# TopLevel.net
KiCad netlist of a schematic drawn in Altium Designer
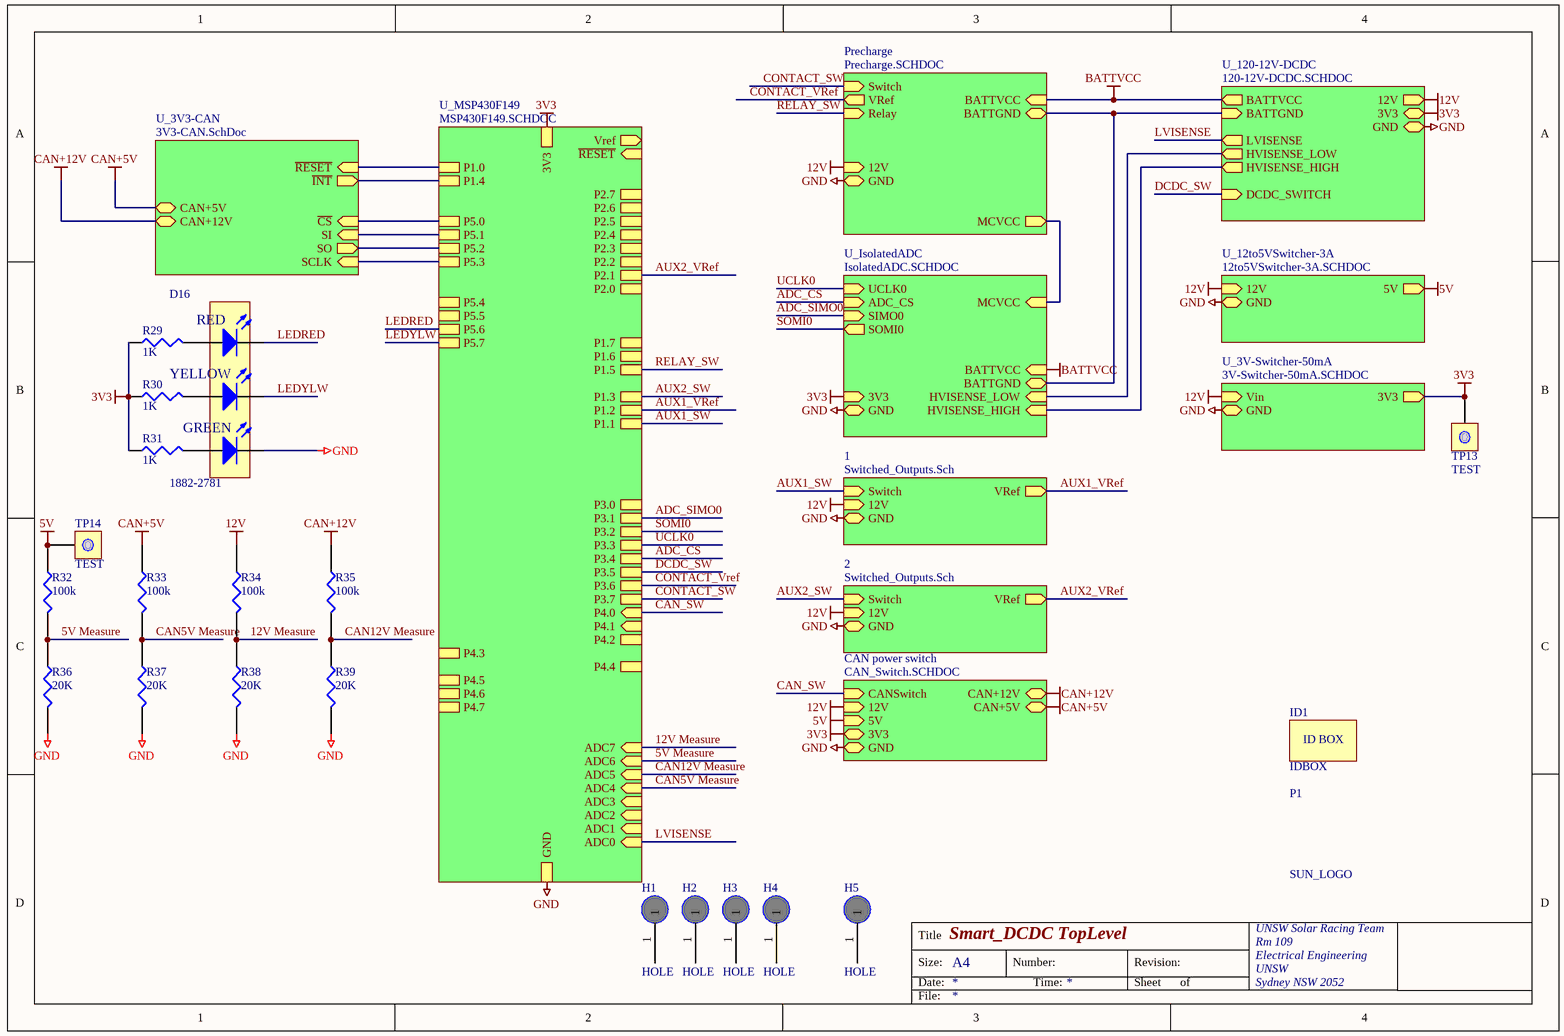
[diagram p0: TopLevel.SCHDOC]

(export (version "E")
  (design (tool "Eeschema 10.0.6"))
  (components
    (comp (ref "D16")
      (value "1882-2781")
      (footprint "LED_TRILEVEL")
      (description "Three level LED")
      (libsource (lib "RCLDQ") (part "LED-TRILEVEL"))
    )
    (comp (ref "H1")
      (value "HOLE")
      (footprint "#6")
      (description "Hole")
      (libsource (lib "Miscellaneous") (part "HOLE"))
    )
    (comp (ref "H2")
      (value "HOLE")
      (footprint "#6")
      (description "Hole")
      (libsource (lib "Miscellaneous") (part "HOLE"))
    )
    (comp (ref "H3")
      (value "HOLE")
      (footprint "#6")
      (description "Hole")
      (libsource (lib "Miscellaneous") (part "HOLE"))
    )
    (comp (ref "H4")
      (value "HOLE")
      (footprint "#6")
      (description "Hole")
      (libsource (lib "Miscellaneous") (part "HOLE"))
    )
    (comp (ref "H5")
      (value "HOLE")
      (footprint "#6")
      (description "Hole")
      (libsource (lib "Miscellaneous") (part "HOLE"))
    )
    (comp (ref "ID1") (value "IDBOX") (footprint "IDBOX") (libsource (lib "Miscellaneous") (part "IDBOX")))
    (comp (ref "P1")
      (value "SUN_LOGO")
      (footprint "SUNSWIFTLOGO")
      (libsource (lib "Miscellaneous") (part "SUN_LOGO"))
    )
    (comp (ref "R29")
      (value "1K")
      (footprint "0603")
      (description "Resistor")
      (libsource (lib "RCLDQ") (part "RES1"))
    )
    (comp (ref "R30")
      (value "1K")
      (footprint "0603")
      (description "Resistor")
      (libsource (lib "RCLDQ") (part "RES1"))
    )
    (comp (ref "R31")
      (value "1K")
      (footprint "0603")
      (description "Resistor")
      (libsource (lib "RCLDQ") (part "RES1"))
    )
    (comp (ref "R32") (value "100k") (footprint "1206") (libsource (lib "*") (part "RES1")))
    (comp (ref "R33") (value "100k") (footprint "1206") (libsource (lib "*") (part "RES1")))
    (comp (ref "R34") (value "100k") (footprint "1206") (libsource (lib "*") (part "RES1")))
    (comp (ref "R35") (value "100k") (footprint "1206") (libsource (lib "*") (part "RES1")))
    (comp (ref "R36") (value "20K") (footprint "1206") (libsource (lib "*") (part "RES1")))
    (comp (ref "R37") (value "20K") (footprint "1206") (libsource (lib "*") (part "RES1")))
    (comp (ref "R38") (value "20K") (footprint "1206") (libsource (lib "*") (part "RES1")))
    (comp (ref "R39") (value "20K") (footprint "1206") (libsource (lib "*") (part "RES1")))
    (comp (ref "TP13")
      (value "TEST")
      (footprint "TESTPOINT")
      (description "TEST POINT")
      (libsource (lib "Miscellaneous") (part "TEST"))
    )
    (comp (ref "TP14")
      (value "TEST")
      (footprint "TESTPOINT")
      (description "TEST POINT")
      (libsource (lib "") (part "TEST_1"))
    )
  )
  (nets
    (net (code "1") (name "/5V Measure") (class "Default")
      (node (ref "R32") (pin "2") (pinfunction "2_2") (pintype "passive"))
      (node (ref "R36") (pin "1") (pinfunction "1_1") (pintype "passive"))
    )
    (net (code "2") (name "/12V Measure") (class "Default")
      (node (ref "R34") (pin "2") (pinfunction "2_2") (pintype "passive"))
      (node (ref "R38") (pin "1") (pinfunction "1_1") (pintype "passive"))
    )
    (net (code "13") (name "/CAN5V Measure") (class "Default")
      (node (ref "R33") (pin "2") (pinfunction "2_2") (pintype "passive"))
      (node (ref "R37") (pin "1") (pinfunction "1_1") (pintype "passive"))
    )
    (net (code "14") (name "/CAN12V Measure") (class "Default")
      (node (ref "R35") (pin "2") (pinfunction "2_2") (pintype "passive"))
      (node (ref "R39") (pin "1") (pinfunction "1_1") (pintype "passive"))
    )
    (net (code "22") (name "/LEDRED") (class "Default")
      (node (ref "D16") (pin "3") (pinfunction "K_3") (pintype "passive"))
    )
    (net (code "23") (name "/LEDYLW") (class "Default")
      (node (ref "D16") (pin "2") (pinfunction "K_2") (pintype "passive"))
    )
    (net (code "56") (name "3V3") (class "Default")
      (node (ref "R29") (pin "1") (pinfunction "1_1") (pintype "passive"))
      (node (ref "R30") (pin "1") (pinfunction "1_1") (pintype "passive"))
      (node (ref "R31") (pin "1") (pinfunction "1_1") (pintype "passive"))
      (node (ref "TP13") (pin "0") (pinfunction "TP_0") (pintype "passive"))
    )
    (net (code "57") (name "5V") (class "Default")
      (node (ref "R32") (pin "1") (pinfunction "1_1") (pintype "passive"))
      (node (ref "TP14") (pin "0") (pinfunction "TP_0") (pintype "passive"))
    )
    (net (code "58") (name "12V") (class "Default")
      (node (ref "R34") (pin "1") (pinfunction "1_1") (pintype "passive"))
    )
    (net (code "60") (name "CAN+5V") (class "Default")
      (node (ref "R33") (pin "1") (pinfunction "1_1") (pintype "passive"))
    )
    (net (code "61") (name "CAN+12V") (class "Default")
      (node (ref "R35") (pin "1") (pinfunction "1_1") (pintype "passive"))
    )
    (net (code "62") (name "GND") (class "Default")
      (node (ref "D16") (pin "1") (pinfunction "K_1") (pintype "passive"))
      (node (ref "R36") (pin "2") (pinfunction "2_2") (pintype "passive"))
      (node (ref "R37") (pin "2") (pinfunction "2_2") (pintype "passive"))
      (node (ref "R38") (pin "2") (pinfunction "2_2") (pintype "passive"))
      (node (ref "R39") (pin "2") (pinfunction "2_2") (pintype "passive"))
    )
    (net (code "63") (name "Net-(D16-A-Pad4)") (class "Default")
      (node (ref "D16") (pin "4") (pinfunction "A_4") (pintype "passive"))
      (node (ref "R29") (pin "2") (pinfunction "2_2") (pintype "passive"))
    )
    (net (code "64") (name "Net-(D16-A-Pad5)") (class "Default")
      (node (ref "D16") (pin "5") (pinfunction "A_5") (pintype "passive"))
      (node (ref "R30") (pin "2") (pinfunction "2_2") (pintype "passive"))
    )
    (net (code "65") (name "Net-(D16-A-Pad6)") (class "Default")
      (node (ref "D16") (pin "6") (pinfunction "A_6") (pintype "passive"))
      (node (ref "R31") (pin "2") (pinfunction "2_2") (pintype "passive"))
    )
    (net (code "66") (name "unconnected-(H1-Pad1)") (class "Default")
      (node (ref "H1") (pin "1") (pinfunction "1_1") (pintype "passive"))
    )
    (net (code "67") (name "unconnected-(H2-Pad1)") (class "Default")
      (node (ref "H2") (pin "1") (pinfunction "1_1") (pintype "passive"))
    )
    (net (code "68") (name "unconnected-(H3-Pad1)") (class "Default")
      (node (ref "H3") (pin "1") (pinfunction "1_1") (pintype "passive"))
    )
    (net (code "69") (name "unconnected-(H4-Pad1)") (class "Default")
      (node (ref "H4") (pin "1") (pinfunction "1_1") (pintype "passive"))
    )
    (net (code "70") (name "unconnected-(H5-Pad1)") (class "Default")
      (node (ref "H5") (pin "1") (pinfunction "1_1") (pintype "passive"))
    )
  )
)
